# ProPrj_Open_Quantum_Front_Cover_2025-07-.net
KiCad netlist of a schematic drawn in EasyEDA Pro
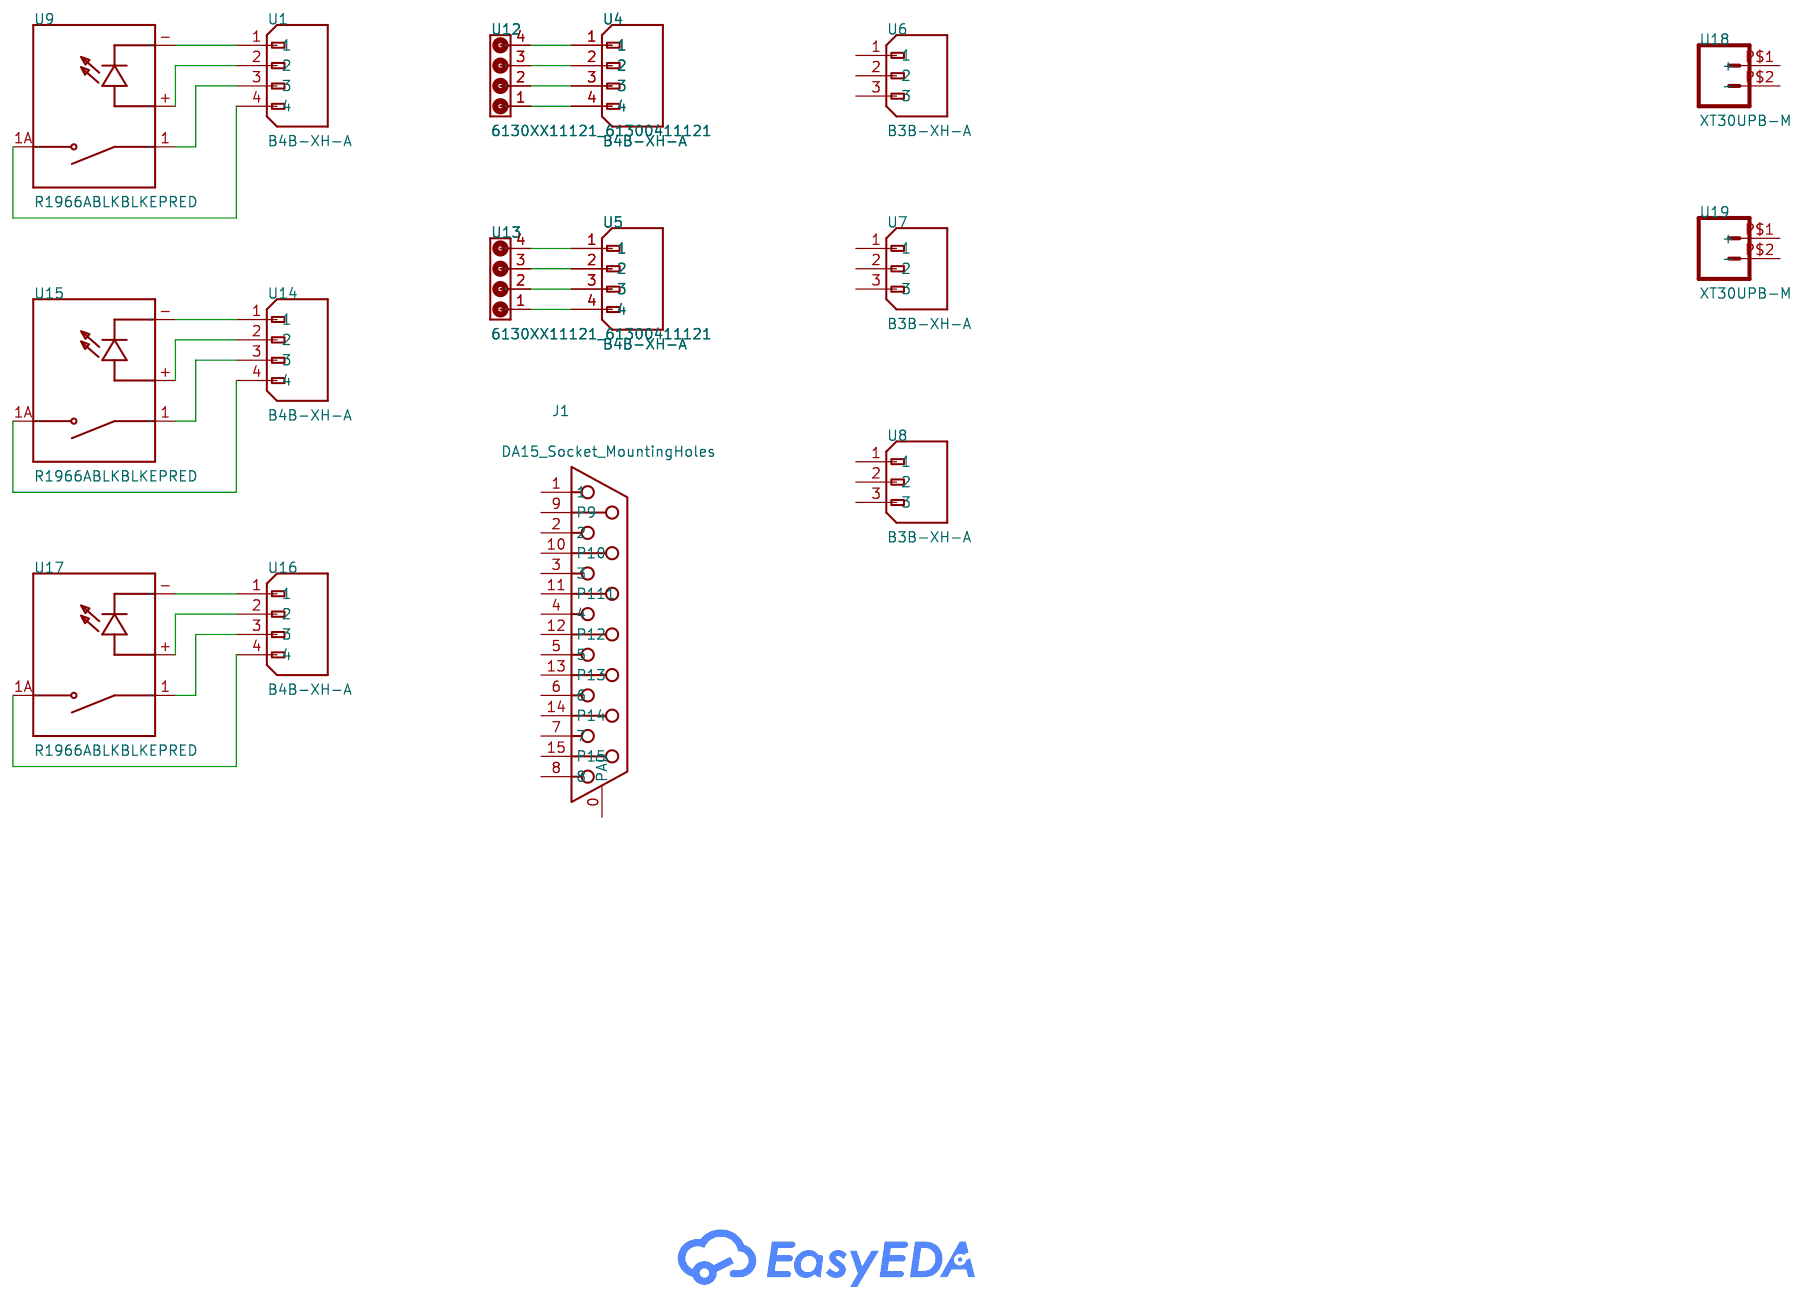
[diagram p0: schematic sheet]

(export (version "E")
  (design (tool "Eeschema 10.0.6"))
  (components
    (comp (ref "J1")
      (value "DA15_Socket_MountingHoles")
      (footprint "easyedapro:Connector_Dsub:DSUB-15_Socket_Vertical_P2.77x2.84mm_MountingHoles")
      (description "15-pin D-SUB connector, socket (female) (low-density/2 columns), Mounting Hole")
      (libsource (lib "easyedapro") (part "Connector_DA15_Socket_MountingHoles"))
    )
    (comp (ref "U1")
      (value "B4B-XH-A")
      (footprint "easyedapro:JST_B4B-XH-A")
      (libsource (lib "easyedapro") (part "B4B-XH-A"))
    )
    (comp (ref "U4")
      (value "B4B-XH-A")
      (footprint "easyedapro:JST_B4B-XH-A")
      (libsource (lib "easyedapro") (part "B4B-XH-A"))
    )
    (comp (ref "U5")
      (value "B4B-XH-A")
      (footprint "easyedapro:JST_B4B-XH-A")
      (libsource (lib "easyedapro") (part "B4B-XH-A"))
    )
    (comp (ref "U6")
      (value "B3B-XH-A")
      (footprint "easyedapro:JST_B3B-XH-A")
      (libsource (lib "easyedapro") (part "B3B-XH-A"))
    )
    (comp (ref "U7")
      (value "B3B-XH-A")
      (footprint "easyedapro:JST_B3B-XH-A")
      (libsource (lib "easyedapro") (part "B3B-XH-A"))
    )
    (comp (ref "U8")
      (value "B3B-XH-A")
      (footprint "easyedapro:JST_B3B-XH-A")
      (libsource (lib "easyedapro") (part "B3B-XH-A"))
    )
    (comp (ref "U9")
      (value "R1966ABLKBLKEPRED")
      (footprint "easyedapro:SW_R1966ABLKBLKEPRED")
      (libsource (lib "easyedapro") (part "R1966ABLKBLKEPRED"))
    )
    (comp (ref "U12")
      (value "6130XX11121_61300411121")
      (footprint "easyedapro:61300411121")
      (libsource (lib "easyedapro") (part "6130XX11121_61300411121"))
    )
    (comp (ref "U13")
      (value "6130XX11121_61300411121")
      (footprint "easyedapro:61300411121")
      (libsource (lib "easyedapro") (part "6130XX11121_61300411121"))
    )
    (comp (ref "U14")
      (value "B4B-XH-A")
      (footprint "easyedapro:JST_B4B-XH-A")
      (libsource (lib "easyedapro") (part "B4B-XH-A"))
    )
    (comp (ref "U15")
      (value "R1966ABLKBLKEPRED")
      (footprint "easyedapro:SW_R1966ABLKBLKEPRED")
      (libsource (lib "easyedapro") (part "R1966ABLKBLKEPRED"))
    )
    (comp (ref "U16")
      (value "B4B-XH-A")
      (footprint "easyedapro:JST_B4B-XH-A")
      (libsource (lib "easyedapro") (part "B4B-XH-A"))
    )
    (comp (ref "U17")
      (value "R1966ABLKBLKEPRED")
      (footprint "easyedapro:SW_R1966ABLKBLKEPRED")
      (libsource (lib "easyedapro") (part "R1966ABLKBLKEPRED"))
    )
    (comp (ref "U18")
      (value "XT30UPB-M")
      (footprint "easyedapro:XT30UPB-M")
      (libsource (lib "easyedapro") (part "XT30UPB-M"))
    )
    (comp (ref "U19")
      (value "XT30UPB-M")
      (footprint "easyedapro:XT30UPB-M")
      (libsource (lib "easyedapro") (part "XT30UPB-M"))
    )
  )
  (nets
    (net (code "1") (name "Net-(U1-Pad3)") (class "Default")
      (node (ref "U1") (pin "3") (pinfunction "3_3") (pintype "unspecified"))
      (node (ref "U9") (pin "1") (pinfunction "1_1") (pintype "unspecified"))
    )
    (net (code "2") (name "Net-(U1-Pad4)") (class "Default")
      (node (ref "U1") (pin "4") (pinfunction "4_4") (pintype "unspecified"))
      (node (ref "U9") (pin "1A") (pinfunction "1A_1A") (pintype "unspecified"))
    )
    (net (code "3") (name "Net-(U9-A)") (class "Default")
      (node (ref "U1") (pin "2") (pinfunction "2_2") (pintype "unspecified"))
      (node (ref "U9") (pin "+") (pinfunction "A_+") (pintype "unspecified"))
    )
    (net (code "4") (name "Net-(U9-C)") (class "Default")
      (node (ref "U1") (pin "1") (pinfunction "1_1") (pintype "unspecified"))
      (node (ref "U9") (pin "-") (pinfunction "C_-") (pintype "unspecified"))
    )
    (net (code "5") (name "Net-(U12-Pad1)") (class "Default")
      (node (ref "U12") (pin "1") (pinfunction "1_1") (pintype "unspecified"))
      (node (ref "U4") (pin "4") (pinfunction "4_4") (pintype "unspecified"))
    )
    (net (code "6") (name "Net-(U12-Pad2)") (class "Default")
      (node (ref "U12") (pin "2") (pinfunction "2_2") (pintype "unspecified"))
      (node (ref "U4") (pin "3") (pinfunction "3_3") (pintype "unspecified"))
    )
    (net (code "7") (name "Net-(U12-Pad3)") (class "Default")
      (node (ref "U12") (pin "3") (pinfunction "3_3") (pintype "unspecified"))
      (node (ref "U4") (pin "2") (pinfunction "2_2") (pintype "unspecified"))
    )
    (net (code "8") (name "Net-(U12-Pad4)") (class "Default")
      (node (ref "U12") (pin "4") (pinfunction "4_4") (pintype "unspecified"))
      (node (ref "U4") (pin "1") (pinfunction "1_1") (pintype "unspecified"))
    )
    (net (code "9") (name "Net-(U13-Pad1)") (class "Default")
      (node (ref "U13") (pin "1") (pinfunction "1_1") (pintype "unspecified"))
      (node (ref "U5") (pin "4") (pinfunction "4_4") (pintype "unspecified"))
    )
    (net (code "10") (name "Net-(U13-Pad2)") (class "Default")
      (node (ref "U13") (pin "2") (pinfunction "2_2") (pintype "unspecified"))
      (node (ref "U5") (pin "3") (pinfunction "3_3") (pintype "unspecified"))
    )
    (net (code "11") (name "Net-(U13-Pad3)") (class "Default")
      (node (ref "U13") (pin "3") (pinfunction "3_3") (pintype "unspecified"))
      (node (ref "U5") (pin "2") (pinfunction "2_2") (pintype "unspecified"))
    )
    (net (code "12") (name "Net-(U13-Pad4)") (class "Default")
      (node (ref "U13") (pin "4") (pinfunction "4_4") (pintype "unspecified"))
      (node (ref "U5") (pin "1") (pinfunction "1_1") (pintype "unspecified"))
    )
    (net (code "13") (name "Net-(U14-Pad3)") (class "Default")
      (node (ref "U14") (pin "3") (pinfunction "3_3") (pintype "unspecified"))
      (node (ref "U15") (pin "1") (pinfunction "1_1") (pintype "unspecified"))
    )
    (net (code "14") (name "Net-(U14-Pad4)") (class "Default")
      (node (ref "U14") (pin "4") (pinfunction "4_4") (pintype "unspecified"))
      (node (ref "U15") (pin "1A") (pinfunction "1A_1A") (pintype "unspecified"))
    )
    (net (code "15") (name "Net-(U15-A)") (class "Default")
      (node (ref "U14") (pin "2") (pinfunction "2_2") (pintype "unspecified"))
      (node (ref "U15") (pin "+") (pinfunction "A_+") (pintype "unspecified"))
    )
    (net (code "16") (name "Net-(U15-C)") (class "Default")
      (node (ref "U14") (pin "1") (pinfunction "1_1") (pintype "unspecified"))
      (node (ref "U15") (pin "-") (pinfunction "C_-") (pintype "unspecified"))
    )
    (net (code "17") (name "Net-(U16-Pad3)") (class "Default")
      (node (ref "U16") (pin "3") (pinfunction "3_3") (pintype "unspecified"))
      (node (ref "U17") (pin "1") (pinfunction "1_1") (pintype "unspecified"))
    )
    (net (code "18") (name "Net-(U16-Pad4)") (class "Default")
      (node (ref "U16") (pin "4") (pinfunction "4_4") (pintype "unspecified"))
      (node (ref "U17") (pin "1A") (pinfunction "1A_1A") (pintype "unspecified"))
    )
    (net (code "19") (name "Net-(U17-A)") (class "Default")
      (node (ref "U16") (pin "2") (pinfunction "2_2") (pintype "unspecified"))
      (node (ref "U17") (pin "+") (pinfunction "A_+") (pintype "unspecified"))
    )
    (net (code "20") (name "Net-(U17-C)") (class "Default")
      (node (ref "U16") (pin "1") (pinfunction "1_1") (pintype "unspecified"))
      (node (ref "U17") (pin "-") (pinfunction "C_-") (pintype "unspecified"))
    )
    (net (code "21") (name "unconnected-(J1-P9-Pad9)") (class "Default")
      (node (ref "J1") (pin "9") (pinfunction "P9_9") (pintype "unspecified"))
    )
    (net (code "22") (name "unconnected-(J1-P10-Pad10)") (class "Default")
      (node (ref "J1") (pin "10") (pinfunction "P10_10") (pintype "unspecified"))
    )
    (net (code "23") (name "unconnected-(J1-P12-Pad12)") (class "Default")
      (node (ref "J1") (pin "12") (pinfunction "P12_12") (pintype "unspecified"))
    )
    (net (code "24") (name "unconnected-(J1-P13-Pad13)") (class "Default")
      (node (ref "J1") (pin "13") (pinfunction "P13_13") (pintype "unspecified"))
    )
    (net (code "25") (name "unconnected-(J1-P14-Pad14)") (class "Default")
      (node (ref "J1") (pin "14") (pinfunction "P14_14") (pintype "unspecified"))
    )
    (net (code "26") (name "unconnected-(J1-P15-Pad15)") (class "Default")
      (node (ref "J1") (pin "15") (pinfunction "P15_15") (pintype "unspecified"))
    )
    (net (code "27") (name "unconnected-(J1-P111-Pad11)") (class "Default")
      (node (ref "J1") (pin "11") (pinfunction "P111_11") (pintype "unspecified"))
    )
    (net (code "28") (name "unconnected-(J1-PAD-Pad0)") (class "Default")
      (node (ref "J1") (pin "0") (pinfunction "PAD_0") (pintype "unspecified"))
    )
    (net (code "29") (name "unconnected-(J1-Pad1)") (class "Default")
      (node (ref "J1") (pin "1") (pinfunction "1_1") (pintype "unspecified"))
    )
    (net (code "30") (name "unconnected-(J1-Pad2)") (class "Default")
      (node (ref "J1") (pin "2") (pinfunction "2_2") (pintype "unspecified"))
    )
    (net (code "31") (name "unconnected-(J1-Pad3)") (class "Default")
      (node (ref "J1") (pin "3") (pinfunction "3_3") (pintype "unspecified"))
    )
    (net (code "32") (name "unconnected-(J1-Pad4)") (class "Default")
      (node (ref "J1") (pin "4") (pinfunction "4_4") (pintype "unspecified"))
    )
    (net (code "33") (name "unconnected-(J1-Pad5)") (class "Default")
      (node (ref "J1") (pin "5") (pinfunction "5_5") (pintype "unspecified"))
    )
    (net (code "34") (name "unconnected-(J1-Pad6)") (class "Default")
      (node (ref "J1") (pin "6") (pinfunction "6_6") (pintype "unspecified"))
    )
    (net (code "35") (name "unconnected-(J1-Pad7)") (class "Default")
      (node (ref "J1") (pin "7") (pinfunction "7_7") (pintype "unspecified"))
    )
    (net (code "36") (name "unconnected-(J1-Pad8)") (class "Default")
      (node (ref "J1") (pin "8") (pinfunction "8_8") (pintype "unspecified"))
    )
    (net (code "37") (name "unconnected-(U6-Pad1)") (class "Default")
      (node (ref "U6") (pin "1") (pinfunction "1_1") (pintype "unspecified"))
    )
    (net (code "38") (name "unconnected-(U6-Pad2)") (class "Default")
      (node (ref "U6") (pin "2") (pinfunction "2_2") (pintype "unspecified"))
    )
    (net (code "39") (name "unconnected-(U6-Pad3)") (class "Default")
      (node (ref "U6") (pin "3") (pinfunction "3_3") (pintype "unspecified"))
    )
    (net (code "40") (name "unconnected-(U7-Pad1)") (class "Default")
      (node (ref "U7") (pin "1") (pinfunction "1_1") (pintype "unspecified"))
    )
    (net (code "41") (name "unconnected-(U7-Pad2)") (class "Default")
      (node (ref "U7") (pin "2") (pinfunction "2_2") (pintype "unspecified"))
    )
    (net (code "42") (name "unconnected-(U7-Pad3)") (class "Default")
      (node (ref "U7") (pin "3") (pinfunction "3_3") (pintype "unspecified"))
    )
    (net (code "43") (name "unconnected-(U8-Pad1)") (class "Default")
      (node (ref "U8") (pin "1") (pinfunction "1_1") (pintype "unspecified"))
    )
    (net (code "44") (name "unconnected-(U8-Pad2)") (class "Default")
      (node (ref "U8") (pin "2") (pinfunction "2_2") (pintype "unspecified"))
    )
    (net (code "45") (name "unconnected-(U8-Pad3)") (class "Default")
      (node (ref "U8") (pin "3") (pinfunction "3_3") (pintype "unspecified"))
    )
    (net (code "46") (name "unconnected-(U18-+-PadP$1)") (class "Default")
      (node (ref "U18") (pin "P$1") (pinfunction "+_P$1") (pintype "unspecified"))
    )
    (net (code "47") (name "unconnected-(U18---PadP$2)") (class "Default")
      (node (ref "U18") (pin "P$2") (pinfunction "-_P$2") (pintype "unspecified"))
    )
    (net (code "48") (name "unconnected-(U19-+-PadP$1)") (class "Default")
      (node (ref "U19") (pin "P$1") (pinfunction "+_P$1") (pintype "unspecified"))
    )
    (net (code "49") (name "unconnected-(U19---PadP$2)") (class "Default")
      (node (ref "U19") (pin "P$2") (pinfunction "-_P$2") (pintype "unspecified"))
    )
  )
)
